# Power_management.net
KiCad netlist of a schematic drawn in Altium Designer
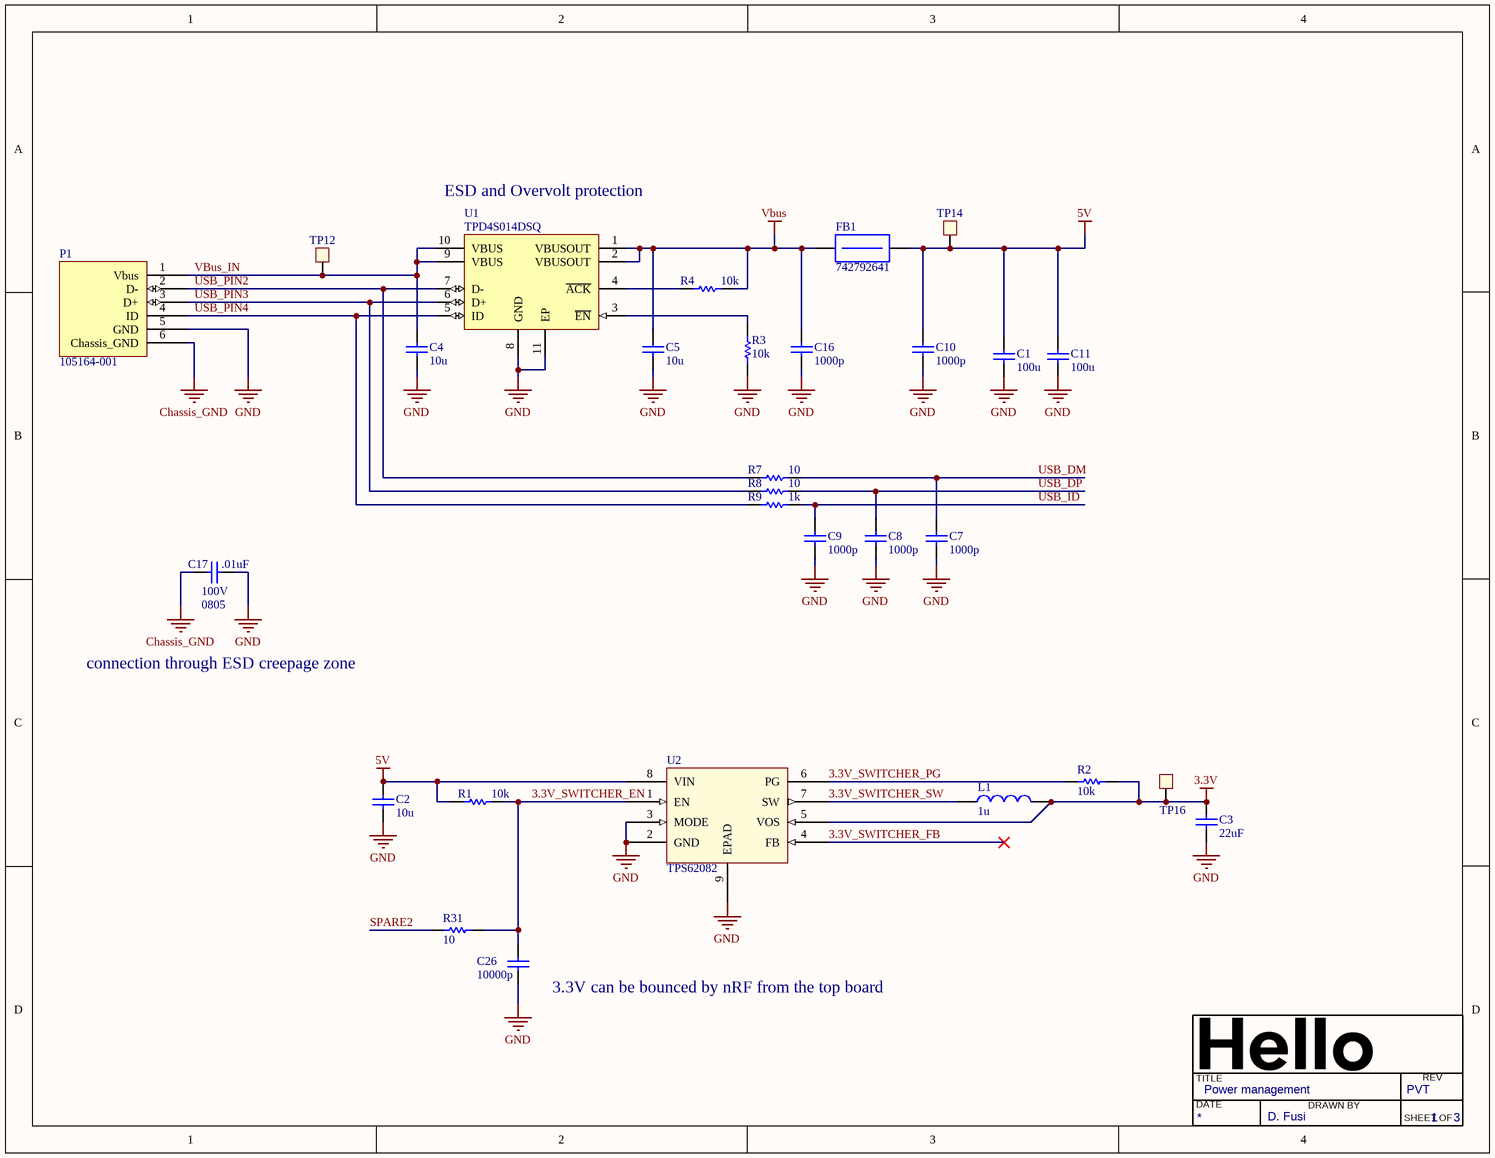
[diagram p0: Power_management.SchDoc]

(export (version "E")
  (design (tool "Eeschema 10.0.6"))
  (components
    (comp (ref "C1")
      (value "100u")
      (footprint "CAP1206_SENSE_DVT")
      (description "CAP CER 10UF 10V 20% X5R 1206")
      (fields (field (name "TOLERANCE") "20%") (field (name "VOLTAGE") "10V"))
      (libsource (lib "Morpheus_pill") (part "C_100u_20_10_X5R_1206"))
    )
    (comp (ref "C2")
      (value "10u")
      (footprint "CAP0603_SENSE_DVT")
      (description "CAP CER 10UF 10V 20% X5R 0603")
      (fields (field (name "TOLERANCE") "20%") (field (name "VOLTAGE") "10V"))
      (libsource (lib "Morpheus_pill") (part "C_10u_20_10_X5R_0603"))
    )
    (comp (ref "C3")
      (value "22uF")
      (footprint "CAP1206_SENSE_DVT")
      (description "CAP CER 22UF 10V 20% X5R 1206")
      (fields (field (name "TOLERANCE") "20%") (field (name "VOLTAGE") "10V"))
      (libsource (lib "Morpheus_pill") (part "C_22u_20_10_X5R_1206"))
    )
    (comp (ref "C4")
      (value "10u")
      (footprint "CAP0603_SENSE_DVT")
      (description "CAP CER 10UF 10V 20% X5R 0603")
      (fields (field (name "TOLERANCE") "20%") (field (name "VOLTAGE") "10V"))
      (libsource (lib "Morpheus_pill") (part "C_10u_20_10_X5R_0603"))
    )
    (comp (ref "C5")
      (value "10u")
      (footprint "CAP0805_SENSE_DVT")
      (description "CAP CER 10UF 10V 10% X7R 0805")
      (fields (field (name "TOLERANCE") "20%") (field (name "VOLTAGE") "10V"))
      (libsource (lib "Morpheus_pill") (part "C_10u_20_10_X7R_0805"))
    )
    (comp (ref "C7")
      (value "1000p")
      (footprint "CAP0402_SENSE_DVT")
      (description "CAP CER 1000PF 50V 10% X7R 0402")
      (fields (field (name "TOLERANCE") "10%") (field (name "VOLTAGE") "50V"))
      (libsource (lib "Morpheus_pill") (part "C_1000p_10_50_X7R_0402"))
    )
    (comp (ref "C8")
      (value "1000p")
      (footprint "CAP0402_SENSE_DVT")
      (description "CAP CER 1000PF 50V 10% X7R 0402")
      (fields (field (name "TOLERANCE") "10%") (field (name "VOLTAGE") "50V"))
      (libsource (lib "Morpheus_pill") (part "C_1000p_10_50_X7R_0402"))
    )
    (comp (ref "C9")
      (value "1000p")
      (footprint "CAP0402_SENSE_DVT")
      (description "CAP CER 1000PF 50V 10% X7R 0402")
      (fields (field (name "TOLERANCE") "10%") (field (name "VOLTAGE") "50V"))
      (libsource (lib "Morpheus_pill") (part "C_1000p_10_50_X7R_0402"))
    )
    (comp (ref "C10")
      (value "1000p")
      (footprint "CAP0402_SENSE_DVT")
      (description "CAP CER 1000PF 50V 10% X7R 0402")
      (fields (field (name "TOLERANCE") "10%") (field (name "VOLTAGE") "50V"))
      (libsource (lib "Morpheus_pill") (part "C_1000p_10_50_X7R_0402"))
    )
    (comp (ref "C11")
      (value "100u")
      (footprint "CAP1206_SENSE_DVT")
      (description "CAP CER 10UF 10V 20% X5R 1206")
      (fields (field (name "TOLERANCE") "20%") (field (name "VOLTAGE") "10V"))
      (libsource (lib "Morpheus_pill") (part "C_100u_20_10_X5R_1206"))
    )
    (comp (ref "C16")
      (value "1000p")
      (footprint "CAP0402_SENSE_DVT")
      (description "CAP CER 1000PF 50V 10% X7R 0402")
      (fields (field (name "TOLERANCE") "10%") (field (name "VOLTAGE") "50V"))
      (libsource (lib "Morpheus_pill") (part "C_1000p_10_50_X7R_0402"))
    )
    (comp (ref "C17")
      (value ".01uF")
      (footprint "CAP0805_SENSE_DVT")
      (description "CAP CER 10000PF 100V X7R 0805")
      (fields (field (name "SIZE") "0805") (field (name "TOLERANCE") "10%") (field (name "VOLTAGE") "100V"))
      (libsource (lib "Morpheus_pill") (part "C_10000p_10_100_X7R_0805"))
    )
    (comp (ref "C26")
      (value "10000p")
      (footprint "CAP0402_SENSE_DVT")
      (description "CAP CER 10000PF 50V 10% X7R 0402")
      (fields (field (name "TOLERANCE") "10%") (field (name "VOLTAGE") "50"))
      (libsource (lib "Morpheus_pill") (part "C_10000p_10_50_X7R_0402"))
    )
    (comp (ref "FB1")
      (value "742792641")
      (footprint "RES0603_SENSE_DVT")
      (description "FERRITE BEAD 300 OHM 2.0A 0603")
      (libsource (lib "Morpheus_pill") (part "FB_300_2_0.15_0603"))
    )
    (comp (ref "L1")
      (value "1u")
      (footprint "INDC3030X13N")
      (description "SMD power inductor, 1uH")
      (fields (field (name "TOLERANCE") "20%"))
      (libsource (lib "Morpheus_pill") (part "L_1u_20_?_0.39_1.4_2.5_1"))
    )
    (comp (ref "P1")
      (value "105164-001")
      (footprint "molex_105164-001")
      (description "Molex right-angle reverse flangeless USB Mini-B OTG receptacle")
      (libsource (lib "Morpheus_pill") (part "molex_105164-001"))
    )
    (comp (ref "R1")
      (value "10k")
      (footprint "RES0402_SENSE_DVT")
      (description "RES SMD 10K OHM 5% 1/16W 0402")
      (fields (field (name "TOLERANCE") "5 %") (field (name "POWER") "1/16W"))
      (libsource (lib "Morpheus_pill") (part "R_10k_5_0.1_0402"))
    )
    (comp (ref "R2")
      (value "10k")
      (footprint "RES0402_SENSE_DVT")
      (description "RES SMD 10K OHM 5% 1/16W 0402")
      (fields (field (name "TOLERANCE") "5 %") (field (name "POWER") "1/16W"))
      (libsource (lib "Morpheus_pill") (part "R_10k_5_0.1_0402"))
    )
    (comp (ref "R3")
      (value "10k")
      (footprint "RES0402_SENSE_DVT")
      (description "RES SMD 10K OHM 5% 1/16W 0402")
      (fields (field (name "TOLERANCE") "5 %") (field (name "POWER") "1/16W"))
      (libsource (lib "Morpheus_pill") (part "R_10k_5_0.1_0402"))
    )
    (comp (ref "R4")
      (value "10k")
      (footprint "RES0402_SENSE_DVT")
      (description "RES SMD 10K OHM 5% 1/16W 0402")
      (fields (field (name "TOLERANCE") "5 %") (field (name "POWER") "1/16W"))
      (libsource (lib "Morpheus_pill") (part "R_10k_5_0.1_0402"))
    )
    (comp (ref "R7")
      (value "10")
      (footprint "RES0402_SENSE_DVT")
      (description "RES SMD 10 OHM 1% 1/16W 0402")
      (fields (field (name "TOLERANCE") "1 %") (field (name "POWER") "1/16W"))
      (libsource (lib "Morpheus_pill") (part "R_10_1_0.1_0402"))
    )
    (comp (ref "R8")
      (value "10")
      (footprint "RES0402_SENSE_DVT")
      (description "RES SMD 10 OHM 1% 1/16W 0402")
      (fields (field (name "TOLERANCE") "1 %") (field (name "POWER") "1/16W"))
      (libsource (lib "Morpheus_pill") (part "R_10_1_0.1_0402"))
    )
    (comp (ref "R9")
      (value "1k")
      (footprint "RES0402_SENSE_DVT")
      (description "RES SMD 1K OHM 1% 1/16W 0402")
      (fields (field (name "TOLERANCE") "1 %") (field (name "POWER") "1/16W"))
      (libsource (lib "Morpheus_pill") (part "R_1k_1_0.1_0402"))
    )
    (comp (ref "R31")
      (value "10")
      (footprint "RES0402_SENSE_DVT")
      (description "RES SMD 10 OHM 1% 1/16W 0402")
      (fields (field (name "TOLERANCE") "1 %") (field (name "POWER") "1/16W"))
      (libsource (lib "Morpheus_pill") (part "R_10_1_0.1_0402"))
    )
    (comp (ref "TP12")
      (value "TP")
      (footprint "TP-1.1")
      (description "testpoint")
      (libsource (lib "Morpheus_pill") (part "TP"))
    )
    (comp (ref "TP14")
      (value "TP")
      (footprint "TP-1.1")
      (description "testpoint")
      (libsource (lib "Morpheus_pill") (part "TP"))
    )
    (comp (ref "TP16")
      (value "TP")
      (footprint "TP-1.1")
      (description "testpoint")
      (libsource (lib "Morpheus_pill") (part "TP"))
    )
    (comp (ref "U1")
      (value "TPD4S014DSQ")
      (footprint "DSQ10-1500X900TP")
      (libsource (lib "Morpheus_pill") (part "TPD4S014DSQ"))
    )
    (comp (ref "U2")
      (value "TPS62082")
      (footprint "QFN50P200X200X80_HS-9N")
      (description "1.2A buck converter with snoozemode")
      (libsource (lib "Morpheus_pill") (part "TPS62082"))
    )
  )
  (nets
    (net (code "1") (name "/3.3V_SWITCHER_EN") (class "Default")
      (node (ref "C26") (pin "2") (pinfunction "2_2") (pintype "passive"))
      (node (ref "R1") (pin "1") (pinfunction "1_1") (pintype "passive"))
      (node (ref "R31") (pin "2") (pinfunction "2_2") (pintype "passive"))
      (node (ref "U2") (pin "1") (pinfunction "EN_1") (pintype "input"))
    )
    (net (code "2") (name "/3.3V_SWITCHER_FB") (class "Default")
      (node (ref "U2") (pin "4") (pinfunction "FB_4") (pintype "input+no_connect"))
    )
    (net (code "3") (name "/3.3V_SWITCHER_PG") (class "Default")
      (node (ref "R2") (pin "2") (pinfunction "2_2") (pintype "passive"))
      (node (ref "U2") (pin "6") (pinfunction "PG_6") (pintype "open_collector"))
    )
    (net (code "4") (name "/3.3V_SWITCHER_SW") (class "Default")
      (node (ref "L1") (pin "1") (pintype "passive"))
      (node (ref "U2") (pin "7") (pinfunction "SW_7") (pintype "output"))
    )
    (net (code "5") (name "/SPARE2") (class "Default")
      (node (ref "R31") (pin "1") (pinfunction "1_1") (pintype "passive"))
    )
    (net (code "6") (name "/USB_DM") (class "Default")
      (node (ref "C7") (pin "2") (pinfunction "2_2") (pintype "passive"))
      (node (ref "R7") (pin "1") (pinfunction "1_1") (pintype "passive"))
    )
    (net (code "7") (name "/USB_DP") (class "Default")
      (node (ref "C8") (pin "2") (pinfunction "2_2") (pintype "passive"))
      (node (ref "R8") (pin "1") (pinfunction "1_1") (pintype "passive"))
    )
    (net (code "8") (name "/USB_ID") (class "Default")
      (node (ref "C9") (pin "2") (pinfunction "2_2") (pintype "passive"))
      (node (ref "R9") (pin "2") (pinfunction "2_2") (pintype "passive"))
    )
    (net (code "9") (name "/USB_PIN2") (class "Default")
      (node (ref "P1") (pin "2") (pinfunction "D-_2") (pintype "bidirectional"))
      (node (ref "R7") (pin "2") (pinfunction "2_2") (pintype "passive"))
      (node (ref "U1") (pin "7") (pinfunction "D-_7") (pintype "bidirectional"))
    )
    (net (code "10") (name "/USB_PIN3") (class "Default")
      (node (ref "P1") (pin "3") (pinfunction "D+_3") (pintype "bidirectional"))
      (node (ref "R8") (pin "2") (pinfunction "2_2") (pintype "passive"))
      (node (ref "U1") (pin "6") (pinfunction "D+_6") (pintype "bidirectional"))
    )
    (net (code "11") (name "/USB_PIN4") (class "Default")
      (node (ref "P1") (pin "4") (pinfunction "ID_4") (pintype "passive"))
      (node (ref "R9") (pin "1") (pinfunction "1_1") (pintype "passive"))
      (node (ref "U1") (pin "5") (pinfunction "ID_5") (pintype "bidirectional"))
    )
    (net (code "12") (name "/VBus_IN") (class "Default")
      (node (ref "C4") (pin "2") (pinfunction "2_2") (pintype "passive"))
      (node (ref "P1") (pin "1") (pinfunction "Vbus_1") (pintype "power_in"))
      (node (ref "TP12") (pin "1") (pinfunction "1_1") (pintype "passive"))
      (node (ref "U1") (pin "10") (pinfunction "VBUS_10") (pintype "power_in"))
      (node (ref "U1") (pin "9") (pinfunction "VBUS_9") (pintype "power_in"))
    )
    (net (code "13") (name "3.3V") (class "Default")
      (node (ref "C3") (pin "2") (pinfunction "2_2") (pintype "passive"))
      (node (ref "L1") (pin "2") (pintype "passive"))
      (node (ref "R2") (pin "1") (pinfunction "1_1") (pintype "passive"))
      (node (ref "TP16") (pin "1") (pinfunction "1_1") (pintype "passive"))
      (node (ref "U2") (pin "5") (pinfunction "VOS_5") (pintype "input"))
    )
    (net (code "14") (name "5V") (class "Default")
      (node (ref "C1") (pin "2") (pinfunction "2_2") (pintype "passive"))
      (node (ref "C10") (pin "2") (pinfunction "2_2") (pintype "passive"))
      (node (ref "C11") (pin "2") (pinfunction "2_2") (pintype "passive"))
      (node (ref "C2") (pin "2") (pinfunction "2_2") (pintype "passive"))
      (node (ref "FB1") (pin "2") (pintype "passive"))
      (node (ref "R1") (pin "2") (pinfunction "2_2") (pintype "passive"))
      (node (ref "TP14") (pin "1") (pinfunction "1_1") (pintype "passive"))
      (node (ref "U2") (pin "8") (pinfunction "VIN_8") (pintype "power_in"))
    )
    (net (code "15") (name "Chassis_GND") (class "Default")
      (node (ref "C17") (pin "1") (pinfunction "1_1") (pintype "passive"))
      (node (ref "P1") (pin "6") (pinfunction "Chassis_GND_6") (pintype "power_in"))
    )
    (net (code "16") (name "GND") (class "Default")
      (node (ref "C1") (pin "1") (pinfunction "1_1") (pintype "passive"))
      (node (ref "C10") (pin "1") (pinfunction "1_1") (pintype "passive"))
      (node (ref "C11") (pin "1") (pinfunction "1_1") (pintype "passive"))
      (node (ref "C16") (pin "1") (pinfunction "1_1") (pintype "passive"))
      (node (ref "C17") (pin "2") (pinfunction "2_2") (pintype "passive"))
      (node (ref "C2") (pin "1") (pinfunction "1_1") (pintype "passive"))
      (node (ref "C26") (pin "1") (pinfunction "1_1") (pintype "passive"))
      (node (ref "C3") (pin "1") (pinfunction "1_1") (pintype "passive"))
      (node (ref "C4") (pin "1") (pinfunction "1_1") (pintype "passive"))
      (node (ref "C5") (pin "1") (pinfunction "1_1") (pintype "passive"))
      (node (ref "C7") (pin "1") (pinfunction "1_1") (pintype "passive"))
      (node (ref "C8") (pin "1") (pinfunction "1_1") (pintype "passive"))
      (node (ref "C9") (pin "1") (pinfunction "1_1") (pintype "passive"))
      (node (ref "P1") (pin "5") (pinfunction "GND_5") (pintype "power_in"))
      (node (ref "R3") (pin "2") (pinfunction "2_2") (pintype "passive"))
      (node (ref "U1") (pin "11") (pinfunction "EP_11") (pintype "power_in"))
      (node (ref "U1") (pin "8") (pinfunction "GND_8") (pintype "power_in"))
      (node (ref "U2") (pin "2") (pinfunction "GND_2") (pintype "power_in"))
      (node (ref "U2") (pin "3") (pinfunction "MODE_3") (pintype "input"))
      (node (ref "U2") (pin "9") (pinfunction "EPAD_9") (pintype "power_in"))
    )
    (net (code "17") (name "Net-(U1-~{ACK})") (class "Default")
      (node (ref "R4") (pin "1") (pinfunction "1_1") (pintype "passive"))
      (node (ref "U1") (pin "4") (pinfunction "~{ACK}_4") (pintype "open_collector"))
    )
    (net (code "18") (name "Net-(U1-~{EN})") (class "Default")
      (node (ref "R3") (pin "1") (pinfunction "1_1") (pintype "passive"))
      (node (ref "U1") (pin "3") (pinfunction "~{EN}_3") (pintype "input"))
    )
    (net (code "19") (name "Vbus") (class "Default")
      (node (ref "C16") (pin "2") (pinfunction "2_2") (pintype "passive"))
      (node (ref "C5") (pin "2") (pinfunction "2_2") (pintype "passive"))
      (node (ref "FB1") (pin "1") (pintype "passive"))
      (node (ref "R4") (pin "2") (pinfunction "2_2") (pintype "passive"))
      (node (ref "U1") (pin "1") (pinfunction "VBUSOUT_1") (pintype "power_in"))
      (node (ref "U1") (pin "2") (pinfunction "VBUSOUT_2") (pintype "power_in"))
    )
  )
)
